# 255sb_to_smd_switch.net
KiCad netlist of a schematic drawn in EAGLE
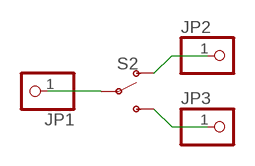
[diagram p0: schematic, sheet 1]

(export (version "E")
  (design (tool "Eeschema 10.0.6"))
  (components
    (comp (ref "JP1")
      (value "PINHD-1X01_2.54-SMD-90°")
      (footprint "eagle-import:1X01SMD_90")
      (libsource (lib "eagle-import") (part "PINHD-1X01_2.54-SMD-90°"))
    )
    (comp (ref "JP2")
      (value "PINHD-1X01_2.54-SMD-90°")
      (footprint "eagle-import:1X01SMD_90")
      (libsource (lib "eagle-import") (part "PINHD-1X01_2.54-SMD-90°"))
    )
    (comp (ref "JP3")
      (value "PINHD-1X01_2.54-SMD-90°")
      (footprint "eagle-import:1X01SMD_90")
      (libsource (lib "eagle-import") (part "PINHD-1X01_2.54-SMD-90°"))
    )
    (comp (ref "S2")
      (value "SWITCH-SPDT-SMD-RIGHT-ANGLE")
      (footprint "eagle-import:SWITCH_SPST_SMD_A")
      (libsource (lib "eagle-import") (part "SWITCH-SPDT-SMD-RIGHT-ANGLE"))
    )
  )
  (nets
    (net (code "1") (name "Net-(S2-O)") (class "Default")
      (node (ref "JP2") (pin "1") (pinfunction "1_1") (pintype "passive"))
      (node (ref "S2") (pin "1") (pinfunction "O_1") (pintype "passive"))
    )
    (net (code "2") (name "Net-(S2-P)") (class "Default")
      (node (ref "JP1") (pin "1") (pinfunction "1_1") (pintype "passive"))
      (node (ref "S2") (pin "2") (pinfunction "P_2") (pintype "passive"))
    )
    (net (code "3") (name "Net-(S2-S)") (class "Default")
      (node (ref "JP3") (pin "1") (pinfunction "1_1") (pintype "passive"))
      (node (ref "S2") (pin "3") (pinfunction "S_3") (pintype "passive"))
    )
  )
)
